# 5V_REG.net
KiCad netlist of a schematic drawn in Altium Designer
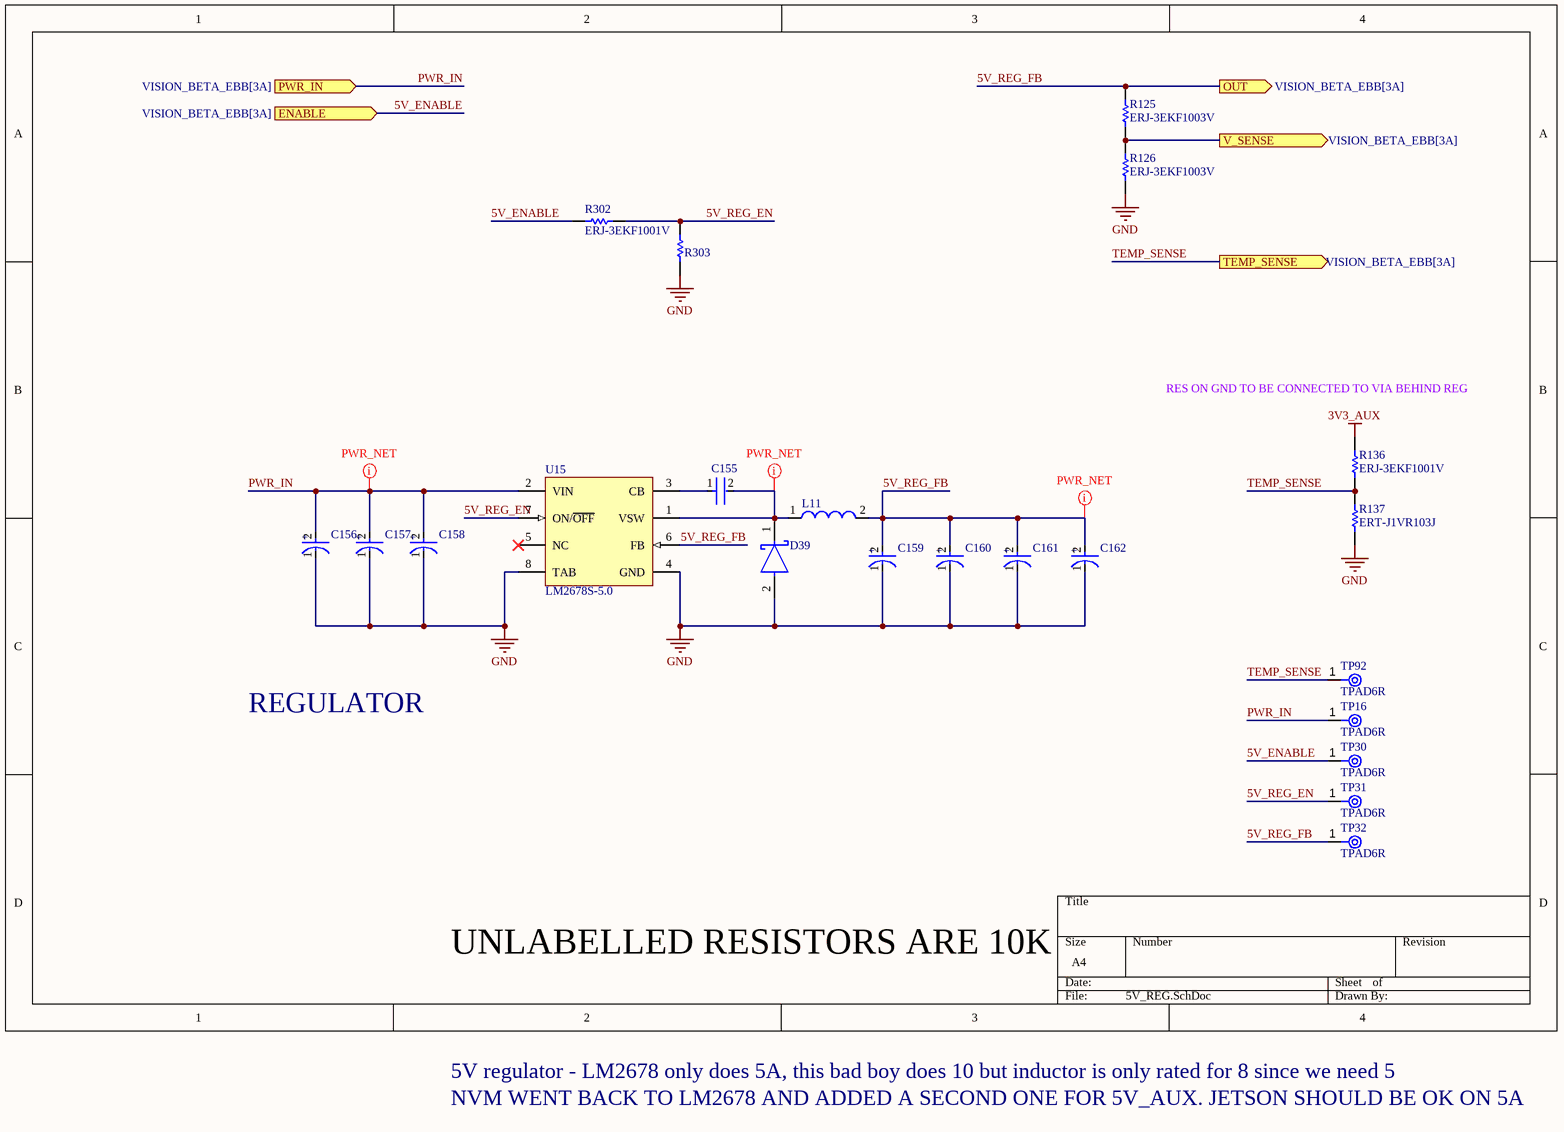
[diagram p0: 5V_REG.SchDoc]

(export (version "E")
  (design (tool "Eeschema 10.0.6"))
  (components
    (comp (ref "C155")
      (value "C0805C103J5RACTU")
      (footprint "FP-C0805C-DN-MFG")
      (description "CAP CER 10000PF 50V X7R 0805")
      (fields
        (field (name "MANUFACTURER") "KEMET")
        (field (name "OCTOPART") "https://octopart.com/c0805c103j5ractu-kemet-133473")
      )
      (libsource (lib "Altium Content Vault") (part "b4654b650e69147ec39a6b967a45e02"))
    )
    (comp (ref "C156")
      (value "20SVP33M")
      (footprint "FP-OS-CON-SMT-E7-MFG")
      (description "Conductive Polymer Aluminum Solid Capacitors (OS-CON) 33uF ±20% 20V RADIAL SMT 8x6.9mm")
      (fields (field (name "VOLTAGE") "20V") (field (name "TOLERANCE") "20%"))
      (libsource (lib "Altium Content Vault") (part "cf48714ba7e38822c1575c7ec0b6d1f"))
    )
    (comp (ref "C157")
      (value "20SVP33M")
      (footprint "FP-OS-CON-SMT-E7-MFG")
      (description "Conductive Polymer Aluminum Solid Capacitors (OS-CON) 33uF ±20% 20V RADIAL SMT 8x6.9mm")
      (fields (field (name "VOLTAGE") "20V") (field (name "TOLERANCE") "20%"))
      (libsource (lib "Altium Content Vault") (part "cf48714ba7e38822c1575c7ec0b6d1f"))
    )
    (comp (ref "C158")
      (value "20SVP33M")
      (footprint "FP-OS-CON-SMT-E7-MFG")
      (description "Conductive Polymer Aluminum Solid Capacitors (OS-CON) 33uF ±20% 20V RADIAL SMT 8x6.9mm")
      (fields (field (name "VOLTAGE") "20V") (field (name "TOLERANCE") "20%"))
      (libsource (lib "Altium Content Vault") (part "cf48714ba7e38822c1575c7ec0b6d1f"))
    )
    (comp (ref "C159")
      (value "EEE-1AA101WR")
      (footprint "FP-SC-MFG")
      (description "CAP ALUM 100UF 20% 10V SMD")
      (fields (field (name "TOLERANCE") "20%"))
      (libsource (lib "Altium Content Vault") (part "a00bbbee19879c290e62620ae7e47b1"))
    )
    (comp (ref "C160")
      (value "EEE-1AA101WR")
      (footprint "FP-SC-MFG")
      (description "CAP ALUM 100UF 20% 10V SMD")
      (fields (field (name "TOLERANCE") "20%"))
      (libsource (lib "Altium Content Vault") (part "a00bbbee19879c290e62620ae7e47b1"))
    )
    (comp (ref "C161")
      (value "EEE-1AA101WR")
      (footprint "FP-SC-MFG")
      (description "CAP ALUM 100UF 20% 10V SMD")
      (fields (field (name "TOLERANCE") "20%"))
      (libsource (lib "Altium Content Vault") (part "a00bbbee19879c290e62620ae7e47b1"))
    )
    (comp (ref "C162")
      (value "EEE-1AA101WR")
      (footprint "FP-SC-MFG")
      (description "CAP ALUM 100UF 20% 10V SMD")
      (fields (field (name "TOLERANCE") "20%"))
      (libsource (lib "Altium Content Vault") (part "a00bbbee19879c290e62620ae7e47b1"))
    )
    (comp (ref "D39")
      (value "B540C-13-F")
      (footprint "FP-SMC-MFG")
      (description "DIODE SCHOTTKY 40V 5A SMC")
      (fields
        (field (name "OCTOPART") "https://octopart.com/b540c-13-f-diodes+inc.-325873")
        (field (name "MANUFACTURER") "Diodes Inc.")
      )
      (libsource (lib "Altium Content Vault") (part "1d6ec82d83fb6aee721767c19dac4b9"))
    )
    (comp (ref "L11")
      (value "74477110")
      (footprint "WE-PD-L")
      (description "SMD-Shielded Power Inductor WE-PD, L = 10.0 µH")
      (libsource (lib "Altium Content Vault") (part "PAS-IND-INDUCTOR-2"))
    )
    (comp (ref "R125")
      (value "ERJ-3EKF1003V")
      (footprint "RESC1608X55X30ML15T15")
      (fields (field (name "MANUFACTURER") "Panasonic"))
      (libsource (lib "Altium Content Vault") (part "RES"))
    )
    (comp (ref "R126")
      (value "ERJ-3EKF1003V")
      (footprint "RESC1608X55X30ML15T15")
      (fields (field (name "MANUFACTURER") "Panasonic"))
      (libsource (lib "Altium Content Vault") (part "RES"))
    )
    (comp (ref "R136")
      (value "ERJ-3EKF1001V")
      (footprint "RESC1608X55X30LL15T15")
      (fields (field (name "MANUFACTURER") "Panasonic"))
      (libsource (lib "Altium Content Vault") (part "RES"))
    )
    (comp (ref "R137")
      (value "ERT-J1VR103J")
      (footprint "RESC1608X90X30ML15T20")
      (fields (field (name "MANUFACTURER") "Panasonic"))
      (libsource (lib "Altium Content Vault") (part "RES"))
    )
    (comp (ref "R302")
      (value "ERJ-3EKF1001V")
      (footprint "RESC1608X55X30LL15T15")
      (fields (field (name "MANUFACTURER") "Panasonic"))
      (libsource (lib "Altium Content Vault") (part "RES"))
    )
    (comp (ref "R303")
      (value "ERJ3EKF1002V")
      (footprint "RESC1609X55X30LL15T15")
      (description "Chip Resistor, 10 KOhm, +/- 1%, 0.1 W, -55 to 155 degC, 0603 (1608 Metric), RoHS, Tape and Reel")
      (fields (field (name "TOLERANCE") "1%") (field (name "MANUFACTURER") "Panasonic"))
      (libsource (lib "Altium Content Vault") (part "RES-2"))
    )
    (comp (ref "TP16")
      (value "TPAD6R")
      (footprint "New footprint 1")
      (description "Test Point .6mm")
      (libsource (lib "Space Concordia") (part "TP"))
    )
    (comp (ref "TP30")
      (value "TPAD6R")
      (footprint "New footprint 1")
      (description "Test Point .6mm")
      (libsource (lib "Space Concordia") (part "TP"))
    )
    (comp (ref "TP31")
      (value "TPAD6R")
      (footprint "New footprint 1")
      (description "Test Point .6mm")
      (libsource (lib "Space Concordia") (part "TP"))
    )
    (comp (ref "TP32")
      (value "TPAD6R")
      (footprint "New footprint 1")
      (description "Test Point .6mm")
      (libsource (lib "Space Concordia") (part "TP"))
    )
    (comp (ref "TP92")
      (value "TPAD6R")
      (footprint "New footprint 1")
      (description "Test Point .6mm")
      (libsource (lib "Space Concordia") (part "TP"))
    )
    (comp (ref "U15")
      (value "LM2678S-5.0")
      (footprint "KTW0007B_N")
      (description "SIMPLE SWITCHER® High Efficiency 5A Step-Down Voltage Regulator, 7-pin TO-263")
      (fields (field (name "MANUFACTURER") "Texas Instruments"))
      (libsource (lib "Altium Content Vault") (part "PM-REG-LM2678S"))
    )
  )
  (nets
    (net (code "1") (name "/5V_ENABLE") (class "Default")
      (node (ref "R302") (pin "1") (pinfunction "1_1") (pintype "passive"))
      (node (ref "TP30") (pin "1") (pinfunction "TP_1") (pintype "passive"))
    )
    (net (code "2") (name "/5V_REG_EN") (class "Default")
      (node (ref "R302") (pin "2") (pinfunction "2_2") (pintype "passive"))
      (node (ref "R303") (pin "2") (pinfunction "2_2") (pintype "passive"))
      (node (ref "TP31") (pin "1") (pinfunction "TP_1") (pintype "passive"))
      (node (ref "U15") (pin "7") (pinfunction "ON/~{OFF}_7") (pintype "input"))
    )
    (net (code "3") (name "/5V_REG_FB") (class "Default")
      (node (ref "C159") (pin "2") (pinfunction "A_2") (pintype "passive"))
      (node (ref "C160") (pin "2") (pinfunction "A_2") (pintype "passive"))
      (node (ref "C161") (pin "2") (pinfunction "A_2") (pintype "passive"))
      (node (ref "C162") (pin "2") (pinfunction "A_2") (pintype "passive"))
      (node (ref "L11") (pin "2") (pinfunction "2_2") (pintype "passive"))
      (node (ref "R125") (pin "2") (pinfunction "2_2") (pintype "passive"))
      (node (ref "TP32") (pin "1") (pinfunction "TP_1") (pintype "passive"))
      (node (ref "U15") (pin "6") (pinfunction "FB_6") (pintype "input"))
    )
    (net (code "4") (name "/PWR_IN") (class "Default")
      (node (ref "C156") (pin "2") (pinfunction "A_2") (pintype "passive"))
      (node (ref "C157") (pin "2") (pinfunction "A_2") (pintype "passive"))
      (node (ref "C158") (pin "2") (pinfunction "A_2") (pintype "passive"))
      (node (ref "TP16") (pin "1") (pinfunction "TP_1") (pintype "passive"))
      (node (ref "U15") (pin "2") (pinfunction "VIN_2") (pintype "power_in"))
    )
    (net (code "5") (name "/TEMP_SENSE") (class "Default")
      (node (ref "R136") (pin "1") (pinfunction "1_1") (pintype "passive"))
      (node (ref "R137") (pin "2") (pinfunction "2_2") (pintype "passive"))
      (node (ref "TP92") (pin "1") (pinfunction "TP_1") (pintype "passive"))
    )
    (net (code "6") (name "/V_SENSE") (class "Default")
      (node (ref "R125") (pin "1") (pinfunction "1_1") (pintype "passive"))
      (node (ref "R126") (pin "2") (pinfunction "2_2") (pintype "passive"))
    )
    (net (code "7") (name "3V3_AUX") (class "Default")
      (node (ref "R136") (pin "2") (pinfunction "2_2") (pintype "passive"))
    )
    (net (code "8") (name "GND") (class "Default")
      (node (ref "C156") (pin "1") (pinfunction "C_1") (pintype "passive"))
      (node (ref "C157") (pin "1") (pinfunction "C_1") (pintype "passive"))
      (node (ref "C158") (pin "1") (pinfunction "C_1") (pintype "passive"))
      (node (ref "C159") (pin "1") (pinfunction "C_1") (pintype "passive"))
      (node (ref "C160") (pin "1") (pinfunction "C_1") (pintype "passive"))
      (node (ref "C161") (pin "1") (pinfunction "C_1") (pintype "passive"))
      (node (ref "C162") (pin "1") (pinfunction "C_1") (pintype "passive"))
      (node (ref "D39") (pin "2") (pinfunction "A_2") (pintype "passive"))
      (node (ref "R126") (pin "1") (pinfunction "1_1") (pintype "passive"))
      (node (ref "R137") (pin "1") (pinfunction "1_1") (pintype "passive"))
      (node (ref "R303") (pin "1") (pinfunction "1_1") (pintype "passive"))
      (node (ref "U15") (pin "4") (pinfunction "GND_4") (pintype "power_in"))
      (node (ref "U15") (pin "8") (pinfunction "TAB_8") (pintype "power_in"))
    )
    (net (code "9") (name "Net-(D39-C)") (class "Default")
      (node (ref "C155") (pin "2") (pinfunction "2_2") (pintype "passive"))
      (node (ref "D39") (pin "1") (pinfunction "C_1") (pintype "passive"))
      (node (ref "L11") (pin "1") (pinfunction "1_1") (pintype "passive"))
      (node (ref "U15") (pin "1") (pinfunction "VSW_1") (pintype "power_in"))
    )
    (net (code "10") (name "Net-(U15-CB)") (class "Default")
      (node (ref "C155") (pin "1") (pinfunction "1_1") (pintype "passive"))
      (node (ref "U15") (pin "3") (pinfunction "CB_3") (pintype "passive"))
    )
    (net (code "11") (name "unconnected-(U15-NC-Pad5)") (class "Default")
      (node (ref "U15") (pin "5") (pinfunction "NC_5") (pintype "passive+no_connect"))
    )
  )
)
